# User_Connectors.net
KiCad netlist of a schematic drawn in Altium Designer
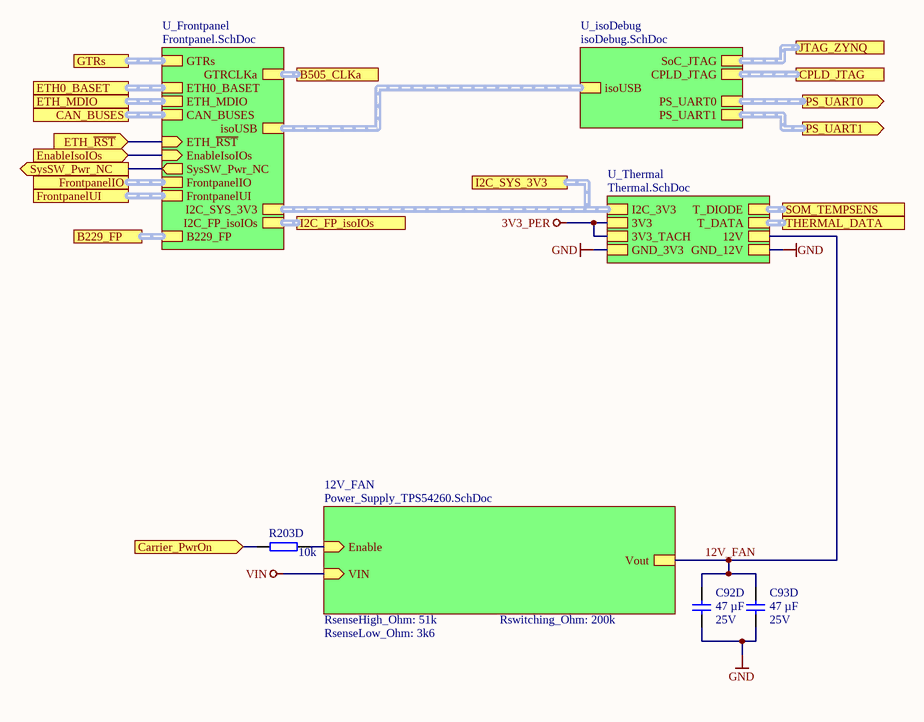
[diagram p0: User_Connectors.SchDoc]

(export (version "E")
  (design (tool "Eeschema 10.0.6"))
  (components
    (comp (ref "C92D")
      (value "47 µF")
      (footprint "C_1206_TE")
      (description "Generic capacitor")
      (fields
        (field (name "TOLERANCE") "10 %")
        (field (name "VOLTAGE") "25V")
        (field (name "MANUFACTURER PART NUMBER") "UZgen_C_1206_47uF_25V_X7R")
        (field (name "CREATED FROM") "UZgenTool")
      )
      (libsource (lib "user") (part "CAP-NP"))
    )
    (comp (ref "C93D")
      (value "47 µF")
      (footprint "C_1206_TE")
      (description "Generic capacitor")
      (fields
        (field (name "TOLERANCE") "10 %")
        (field (name "VOLTAGE") "25V")
        (field (name "MANUFACTURER PART NUMBER") "UZgen_C_1206_47uF_25V_X7R")
        (field (name "CREATED FROM") "UZgenTool")
      )
      (libsource (lib "user") (part "CAP-NP"))
    )
    (comp (ref "R203D")
      (value "10k")
      (footprint "R_0603_TE")
      (description "Generic resistor")
      (fields
        (field (name "TOLERANCE") "1 %")
        (field (name "MANUFACTURER PART NUMBER") "UZgen_R_0603_10k")
        (field (name "CREATED FROM") "AGeiger")
      )
      (libsource (lib "user") (part "RES"))
    )
  )
  (nets
    (net (code "17") (name "/12V_FAN") (class "Default")
      (node (ref "C92D") (pin "2") (pinfunction "2_2") (pintype "passive"))
      (node (ref "C93D") (pin "2") (pinfunction "2_2") (pintype "passive"))
    )
    (net (code "22") (name "/Carrier_PwrOn") (class "Default")
      (node (ref "R203D") (pin "1") (pinfunction "1_1") (pintype "passive"))
    )
    (net (code "26") (name "/Enable") (class "Default")
      (node (ref "R203D") (pin "2") (pinfunction "2_2") (pintype "passive"))
    )
    (net (code "41") (name "GND") (class "Default")
      (node (ref "C92D") (pin "1") (pinfunction "1_1") (pintype "passive"))
      (node (ref "C93D") (pin "1") (pinfunction "1_1") (pintype "passive"))
    )
  )
)
